# ProPrj_VE7GGH_CW_USB_TRS_2026-06-29.net
KiCad netlist of a schematic drawn in EasyEDA Pro
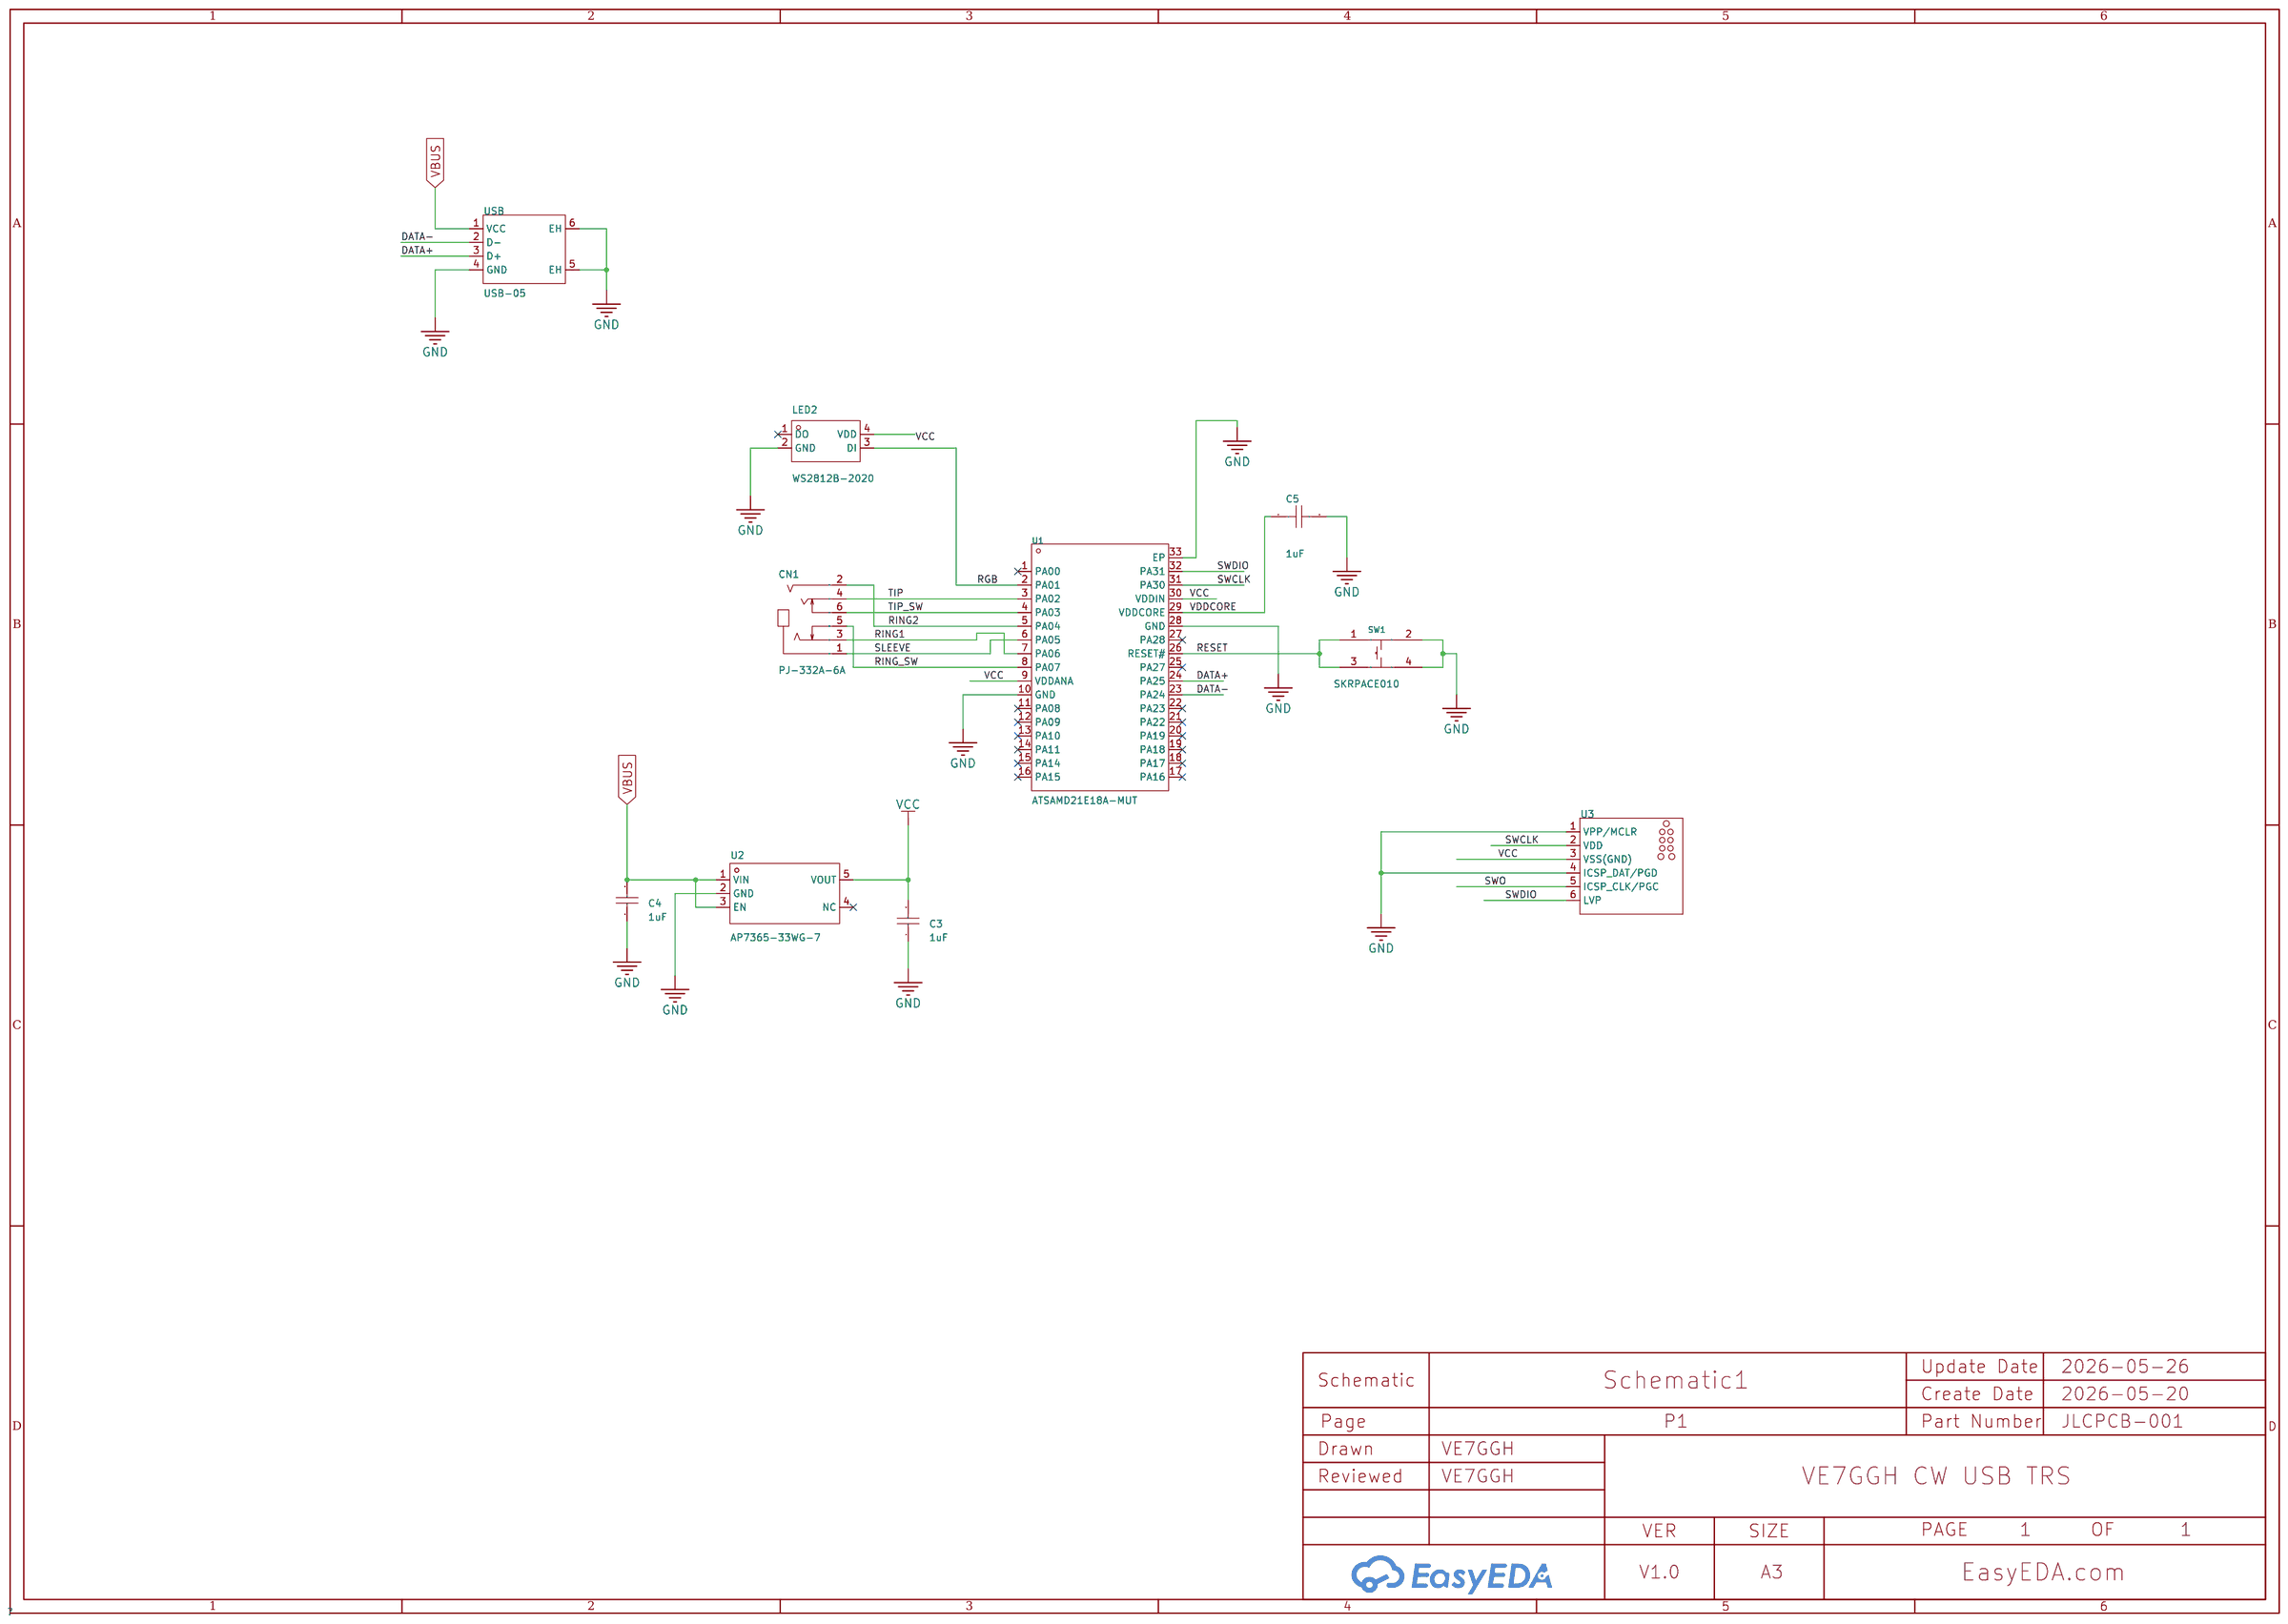
[diagram p0: schematic sheet]

(export (version "E")
  (design (tool "Eeschema 10.0.6"))
  (components
    (comp (ref "C3")
      (value "1uF")
      (footprint "easyedapro:C0603")
      (description "Capacitance:1uF Tolerance:±10% Tolerance:±10% Voltage Rating:10V Temperature Coefficient:X5R")
      (fields
        (field (name "Manufacturer Part") "CC0603KRX5R6BB105")
        (field (name "Manufacturer") "YAGEO(国巨)")
      )
      (libsource (lib "easyedapro") (part "CC0603KRX5R6BB105"))
    )
    (comp (ref "C4")
      (value "1uF")
      (footprint "easyedapro:C0603")
      (description "Capacitance:1uF Tolerance:±10% Tolerance:±10% Voltage Rating:10V Temperature Coefficient:X5R")
      (fields
        (field (name "Manufacturer Part") "CC0603KRX5R6BB105")
        (field (name "Manufacturer") "YAGEO(国巨)")
      )
      (libsource (lib "easyedapro") (part "CC0603KRX5R6BB105"))
    )
    (comp (ref "C5")
      (value "1uF")
      (footprint "easyedapro:C0603")
      (description "Capacitance:1uF Tolerance:±10% Tolerance:±10% Voltage Rating:50V Temperature Coefficient:X7R")
      (fields
        (field (name "Manufacturer Part") "CC0603KRX7R9BB105")
        (field (name "Manufacturer") "YAGEO(国巨)")
      )
      (libsource (lib "easyedapro") (part "CC0603KRX7R9BB105"))
    )
    (comp (ref "CN1")
      (value "PJ-332A-6A")
      (footprint "easyedapro:AUDIO-SMD_PJ-332A-6A")
      (fields (field (name "Manufacturer") "韩国韩荣"))
      (libsource (lib "easyedapro") (part "PJ-332A-6A"))
    )
    (comp (ref "LED2")
      (value "WS2812B-2020")
      (footprint "easyedapro:LED-SMD_4P-L2.0-W2.0-TL_WS2812B-2020")
      (fields (field (name "Manufacturer") "worldsemi"))
      (libsource (lib "easyedapro") (part "WS2812B-2020"))
    )
    (comp (ref "SW1")
      (value "SKRPACE010")
      (footprint "easyedapro:KEY-SMD_4P-L4.2-W3.2-P2.20-LS4.6")
      (fields (field (name "Manufacturer") "ALPSALPINE(阿尔卑斯阿尔派)"))
      (libsource (lib "easyedapro") (part "SKRPACE010"))
    )
    (comp (ref "U1")
      (value "ATSAMD21E18A-MUT")
      (footprint "easyedapro:QFN-32_L5.0-W5.0-P0.50-TL-EP3.6")
      (fields (field (name "Manufacturer") "MICROCHIP(美国微芯)"))
      (libsource (lib "easyedapro") (part "ATSAMD21E18A-MUT_C2052801"))
    )
    (comp (ref "U2")
      (value "AP7365-33WG-7")
      (footprint "easyedapro:SOT-25_L3.0-W1.6-P0.95-LS2.8-BR")
      (fields (field (name "Manufacturer") "DIODES(美台)"))
      (libsource (lib "easyedapro") (part "AP7365-33WG-7"))
    )
    (comp (ref "U3") (value "~") (libsource (lib "easyedapro") (part "TC2030_-MCP-NL")))
    (comp (ref "USB")
      (value "USB-05")
      (footprint "easyedapro:USB-A-TH_USB-05")
      (fields (field (name "Manufacturer") "SOFNG(硕方)"))
      (libsource (lib "easyedapro") (part "USB-05"))
    )
  )
  (nets
    (net (code "1") (name "/DATA+") (class "Default")
      (node (ref "U1") (pin "24") (pinfunction "PA25_24") (pintype "input"))
      (node (ref "USB") (pin "3") (pinfunction "D+_3") (pintype "input"))
    )
    (net (code "2") (name "/DATA-") (class "Default")
      (node (ref "U1") (pin "23") (pinfunction "PA24_23") (pintype "input"))
      (node (ref "USB") (pin "2") (pinfunction "D-_2") (pintype "input"))
    )
    (net (code "3") (name "/RESET") (class "Default")
      (node (ref "SW1") (pin "1") (pinfunction "1_1") (pintype "input"))
      (node (ref "SW1") (pin "3") (pinfunction "3_3") (pintype "input"))
      (node (ref "U1") (pin "26") (pinfunction "RESET#_26") (pintype "input"))
    )
    (net (code "4") (name "/RGB") (class "Default")
      (node (ref "LED2") (pin "3") (pinfunction "DI_3") (pintype "unspecified"))
      (node (ref "U1") (pin "2") (pinfunction "PA01_2") (pintype "input"))
    )
    (net (code "5") (name "/RING1") (class "Default")
      (node (ref "CN1") (pin "3") (pinfunction "3_3") (pintype "input"))
      (node (ref "U1") (pin "7") (pinfunction "PA06_7") (pintype "input"))
    )
    (net (code "6") (name "/RING2") (class "Default")
      (node (ref "CN1") (pin "2") (pinfunction "2_2") (pintype "input"))
      (node (ref "U1") (pin "5") (pinfunction "PA04_5") (pintype "input"))
    )
    (net (code "7") (name "/RING_SW") (class "Default")
      (node (ref "CN1") (pin "5") (pinfunction "5_5") (pintype "input"))
      (node (ref "U1") (pin "8") (pinfunction "PA07_8") (pintype "input"))
    )
    (net (code "8") (name "/SLEEVE") (class "Default")
      (node (ref "CN1") (pin "1") (pinfunction "1_1") (pintype "input"))
      (node (ref "U1") (pin "6") (pinfunction "PA05_6") (pintype "input"))
    )
    (net (code "9") (name "/SWCLK") (class "Default")
      (node (ref "U1") (pin "31") (pinfunction "PA30_31") (pintype "input"))
      (node (ref "U3") (pin "2") (pinfunction "VDD_2") (pintype "unspecified"))
    )
    (net (code "10") (name "/SWDIO") (class "Default")
      (node (ref "U1") (pin "32") (pinfunction "PA31_32") (pintype "input"))
      (node (ref "U3") (pin "6") (pinfunction "LVP_6") (pintype "bidirectional"))
    )
    (net (code "11") (name "/SWO") (class "Default")
      (node (ref "U3") (pin "5") (pinfunction "ICSP_CLK/PGC_5") (pintype "output"))
    )
    (net (code "12") (name "/TIP") (class "Default")
      (node (ref "CN1") (pin "4") (pinfunction "4_4") (pintype "input"))
      (node (ref "U1") (pin "3") (pinfunction "PA02_3") (pintype "input"))
    )
    (net (code "13") (name "/TIP_SW") (class "Default")
      (node (ref "CN1") (pin "6") (pinfunction "6_6") (pintype "input"))
      (node (ref "U1") (pin "4") (pinfunction "PA03_4") (pintype "input"))
    )
    (net (code "14") (name "/VDDCORE") (class "Default")
      (node (ref "C5") (pin "1") (pinfunction "1_1") (pintype "unspecified"))
      (node (ref "U1") (pin "29") (pinfunction "VDDCORE_29") (pintype "input"))
    )
    (net (code "15") (name "GND") (class "Default")
      (node (ref "C3") (pin "1") (pinfunction "1_1") (pintype "input"))
      (node (ref "C4") (pin "1") (pinfunction "1_1") (pintype "input"))
      (node (ref "C5") (pin "2") (pinfunction "2_2") (pintype "unspecified"))
      (node (ref "LED2") (pin "2") (pinfunction "GND_2") (pintype "unspecified"))
      (node (ref "SW1") (pin "2") (pinfunction "2_2") (pintype "input"))
      (node (ref "SW1") (pin "4") (pinfunction "4_4") (pintype "input"))
      (node (ref "U1") (pin "10") (pinfunction "GND_10") (pintype "input"))
      (node (ref "U1") (pin "28") (pinfunction "GND_28") (pintype "input"))
      (node (ref "U1") (pin "33") (pinfunction "EP_33") (pintype "input"))
      (node (ref "U2") (pin "2") (pinfunction "GND_2") (pintype "unspecified"))
      (node (ref "U3") (pin "1") (pinfunction "VPP/MCLR_1") (pintype "unspecified"))
      (node (ref "U3") (pin "4") (pinfunction "ICSP_DAT/PGD_4") (pintype "bidirectional"))
      (node (ref "USB") (pin "4") (pinfunction "GND_4") (pintype "input"))
      (node (ref "USB") (pin "5") (pinfunction "EH_5") (pintype "unspecified"))
      (node (ref "USB") (pin "6") (pinfunction "EH_6") (pintype "unspecified"))
    )
    (net (code "16") (name "VBUS") (class "Default")
      (node (ref "C4") (pin "2") (pinfunction "2_2") (pintype "input"))
      (node (ref "U2") (pin "1") (pinfunction "VIN_1") (pintype "unspecified"))
      (node (ref "U2") (pin "3") (pinfunction "EN_3") (pintype "unspecified"))
      (node (ref "USB") (pin "1") (pinfunction "VCC_1") (pintype "input"))
    )
    (net (code "17") (name "VCC") (class "Default")
      (node (ref "C3") (pin "2") (pinfunction "2_2") (pintype "input"))
      (node (ref "LED2") (pin "4") (pinfunction "VDD_4") (pintype "unspecified"))
      (node (ref "U1") (pin "30") (pinfunction "VDDIN_30") (pintype "input"))
      (node (ref "U1") (pin "9") (pinfunction "VDDANA_9") (pintype "input"))
      (node (ref "U2") (pin "5") (pinfunction "VOUT_5") (pintype "unspecified"))
      (node (ref "U3") (pin "3") (pinfunction "VSS(GND)_3") (pintype "unspecified"))
    )
    (net (code "18") (name "unconnected-(LED2-DO-Pad1)") (class "Default")
      (node (ref "LED2") (pin "1") (pinfunction "DO_1") (pintype "unspecified+no_connect"))
    )
    (net (code "19") (name "unconnected-(U1-PA00-Pad1)") (class "Default")
      (node (ref "U1") (pin "1") (pinfunction "PA00_1") (pintype "input+no_connect"))
    )
    (net (code "20") (name "unconnected-(U1-PA08-Pad11)") (class "Default")
      (node (ref "U1") (pin "11") (pinfunction "PA08_11") (pintype "input+no_connect"))
    )
    (net (code "21") (name "unconnected-(U1-PA09-Pad12)") (class "Default")
      (node (ref "U1") (pin "12") (pinfunction "PA09_12") (pintype "input+no_connect"))
    )
    (net (code "22") (name "unconnected-(U1-PA10-Pad13)") (class "Default")
      (node (ref "U1") (pin "13") (pinfunction "PA10_13") (pintype "input+no_connect"))
    )
    (net (code "23") (name "unconnected-(U1-PA11-Pad14)") (class "Default")
      (node (ref "U1") (pin "14") (pinfunction "PA11_14") (pintype "input+no_connect"))
    )
    (net (code "24") (name "unconnected-(U1-PA14-Pad15)") (class "Default")
      (node (ref "U1") (pin "15") (pinfunction "PA14_15") (pintype "input+no_connect"))
    )
    (net (code "25") (name "unconnected-(U1-PA15-Pad16)") (class "Default")
      (node (ref "U1") (pin "16") (pinfunction "PA15_16") (pintype "input+no_connect"))
    )
    (net (code "26") (name "unconnected-(U1-PA16-Pad17)") (class "Default")
      (node (ref "U1") (pin "17") (pinfunction "PA16_17") (pintype "input+no_connect"))
    )
    (net (code "27") (name "unconnected-(U1-PA17-Pad18)") (class "Default")
      (node (ref "U1") (pin "18") (pinfunction "PA17_18") (pintype "input+no_connect"))
    )
    (net (code "28") (name "unconnected-(U1-PA18-Pad19)") (class "Default")
      (node (ref "U1") (pin "19") (pinfunction "PA18_19") (pintype "input+no_connect"))
    )
    (net (code "29") (name "unconnected-(U1-PA19-Pad20)") (class "Default")
      (node (ref "U1") (pin "20") (pinfunction "PA19_20") (pintype "input+no_connect"))
    )
    (net (code "30") (name "unconnected-(U1-PA22-Pad21)") (class "Default")
      (node (ref "U1") (pin "21") (pinfunction "PA22_21") (pintype "input+no_connect"))
    )
    (net (code "31") (name "unconnected-(U1-PA23-Pad22)") (class "Default")
      (node (ref "U1") (pin "22") (pinfunction "PA23_22") (pintype "input+no_connect"))
    )
    (net (code "32") (name "unconnected-(U1-PA27-Pad25)") (class "Default")
      (node (ref "U1") (pin "25") (pinfunction "PA27_25") (pintype "input+no_connect"))
    )
    (net (code "33") (name "unconnected-(U1-PA28-Pad27)") (class "Default")
      (node (ref "U1") (pin "27") (pinfunction "PA28_27") (pintype "input+no_connect"))
    )
    (net (code "34") (name "unconnected-(U2-NC-Pad4)") (class "Default")
      (node (ref "U2") (pin "4") (pinfunction "NC_4") (pintype "unspecified+no_connect"))
    )
  )
)
